# moja-row.net
KiCad netlist of a schematic drawn in EAGLE
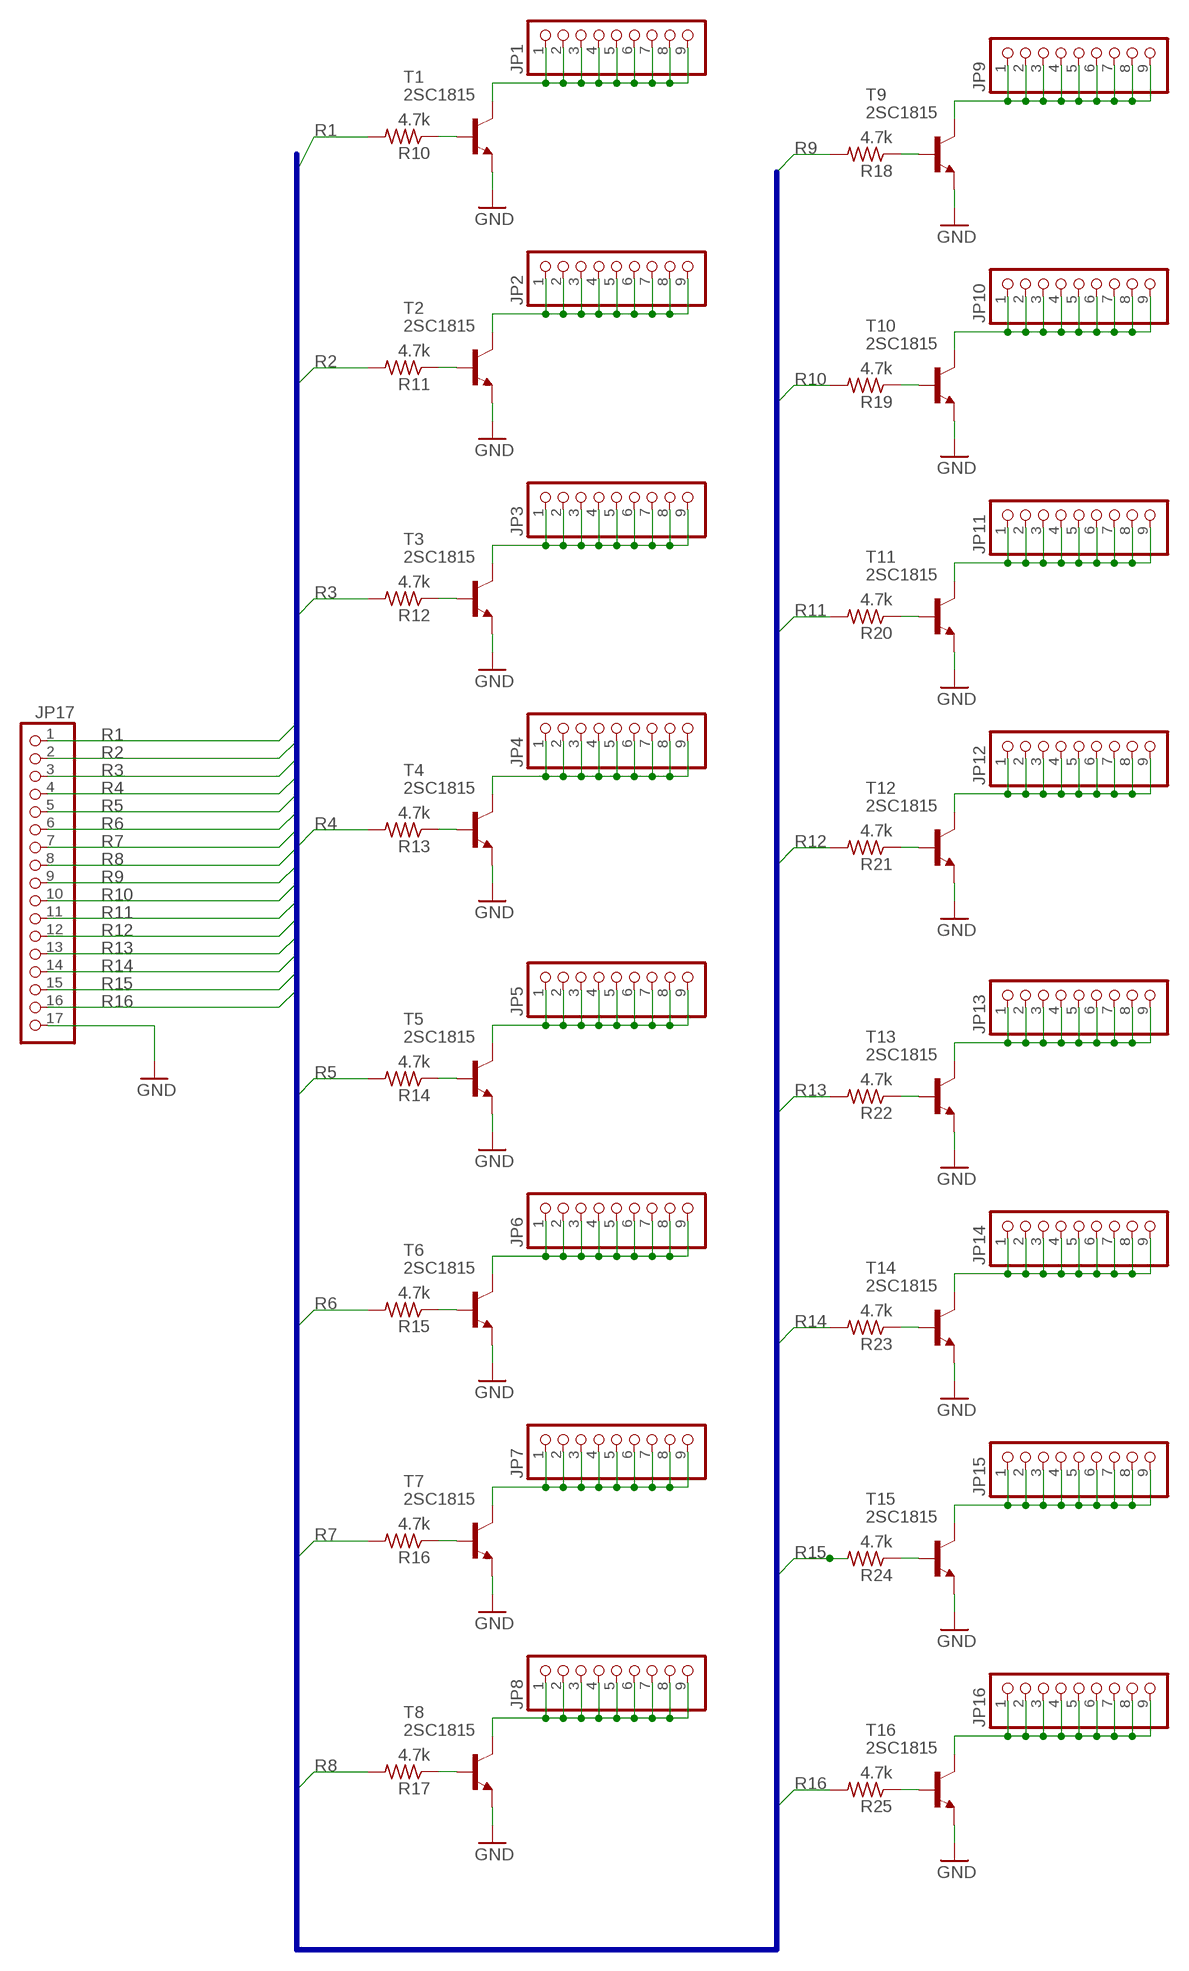
[diagram p0: schematic, sheet 1]

(export (version "E")
  (design (tool "Eeschema 10.0.6"))
  (components
    (comp (ref "JP1")
      (value "PINHD-1X9")
      (footprint "eagle-import:1X09")
      (libsource (lib "eagle-import") (part "PINHD-1X9"))
    )
    (comp (ref "JP2")
      (value "PINHD-1X9")
      (footprint "eagle-import:1X09")
      (libsource (lib "eagle-import") (part "PINHD-1X9"))
    )
    (comp (ref "JP3")
      (value "PINHD-1X9")
      (footprint "eagle-import:1X09")
      (libsource (lib "eagle-import") (part "PINHD-1X9"))
    )
    (comp (ref "JP4")
      (value "PINHD-1X9")
      (footprint "eagle-import:1X09")
      (libsource (lib "eagle-import") (part "PINHD-1X9"))
    )
    (comp (ref "JP5")
      (value "PINHD-1X9")
      (footprint "eagle-import:1X09")
      (libsource (lib "eagle-import") (part "PINHD-1X9"))
    )
    (comp (ref "JP6")
      (value "PINHD-1X9")
      (footprint "eagle-import:1X09")
      (libsource (lib "eagle-import") (part "PINHD-1X9"))
    )
    (comp (ref "JP7")
      (value "PINHD-1X9")
      (footprint "eagle-import:1X09")
      (libsource (lib "eagle-import") (part "PINHD-1X9"))
    )
    (comp (ref "JP8")
      (value "PINHD-1X9")
      (footprint "eagle-import:1X09")
      (libsource (lib "eagle-import") (part "PINHD-1X9"))
    )
    (comp (ref "JP9")
      (value "PINHD-1X9")
      (footprint "eagle-import:1X09")
      (libsource (lib "eagle-import") (part "PINHD-1X9"))
    )
    (comp (ref "JP10")
      (value "PINHD-1X9")
      (footprint "eagle-import:1X09")
      (libsource (lib "eagle-import") (part "PINHD-1X9"))
    )
    (comp (ref "JP11")
      (value "PINHD-1X9")
      (footprint "eagle-import:1X09")
      (libsource (lib "eagle-import") (part "PINHD-1X9"))
    )
    (comp (ref "JP12")
      (value "PINHD-1X9")
      (footprint "eagle-import:1X09")
      (libsource (lib "eagle-import") (part "PINHD-1X9"))
    )
    (comp (ref "JP13")
      (value "PINHD-1X9")
      (footprint "eagle-import:1X09")
      (libsource (lib "eagle-import") (part "PINHD-1X9"))
    )
    (comp (ref "JP14")
      (value "PINHD-1X9")
      (footprint "eagle-import:1X09")
      (libsource (lib "eagle-import") (part "PINHD-1X9"))
    )
    (comp (ref "JP15")
      (value "PINHD-1X9")
      (footprint "eagle-import:1X09")
      (libsource (lib "eagle-import") (part "PINHD-1X9"))
    )
    (comp (ref "JP16")
      (value "PINHD-1X9")
      (footprint "eagle-import:1X09")
      (libsource (lib "eagle-import") (part "PINHD-1X9"))
    )
    (comp (ref "JP17")
      (value "PINHD-1X17")
      (footprint "eagle-import:1X17")
      (libsource (lib "eagle-import") (part "PINHD-1X17"))
    )
    (comp (ref "R10")
      (value "4.7k")
      (footprint "eagle-import:0204V")
      (libsource (lib "eagle-import") (part "R-US_0204/2V"))
    )
    (comp (ref "R11")
      (value "4.7k")
      (footprint "eagle-import:0204V")
      (libsource (lib "eagle-import") (part "R-US_0204/2V"))
    )
    (comp (ref "R12")
      (value "4.7k")
      (footprint "eagle-import:0204V")
      (libsource (lib "eagle-import") (part "R-US_0204/2V"))
    )
    (comp (ref "R13")
      (value "4.7k")
      (footprint "eagle-import:0204V")
      (libsource (lib "eagle-import") (part "R-US_0204/2V"))
    )
    (comp (ref "R14")
      (value "4.7k")
      (footprint "eagle-import:0204V")
      (libsource (lib "eagle-import") (part "R-US_0204/2V"))
    )
    (comp (ref "R15")
      (value "4.7k")
      (footprint "eagle-import:0204V")
      (libsource (lib "eagle-import") (part "R-US_0204/2V"))
    )
    (comp (ref "R16")
      (value "4.7k")
      (footprint "eagle-import:0204V")
      (libsource (lib "eagle-import") (part "R-US_0204/2V"))
    )
    (comp (ref "R17")
      (value "4.7k")
      (footprint "eagle-import:0204V")
      (libsource (lib "eagle-import") (part "R-US_0204/2V"))
    )
    (comp (ref "R18")
      (value "4.7k")
      (footprint "eagle-import:0204V")
      (libsource (lib "eagle-import") (part "R-US_0204/2V"))
    )
    (comp (ref "R19")
      (value "4.7k")
      (footprint "eagle-import:0204V")
      (libsource (lib "eagle-import") (part "R-US_0204/2V"))
    )
    (comp (ref "R20")
      (value "4.7k")
      (footprint "eagle-import:0204V")
      (libsource (lib "eagle-import") (part "R-US_0204/2V"))
    )
    (comp (ref "R21")
      (value "4.7k")
      (footprint "eagle-import:0204V")
      (libsource (lib "eagle-import") (part "R-US_0204/2V"))
    )
    (comp (ref "R22")
      (value "4.7k")
      (footprint "eagle-import:0204V")
      (libsource (lib "eagle-import") (part "R-US_0204/2V"))
    )
    (comp (ref "R23")
      (value "4.7k")
      (footprint "eagle-import:0204V")
      (libsource (lib "eagle-import") (part "R-US_0204/2V"))
    )
    (comp (ref "R24")
      (value "4.7k")
      (footprint "eagle-import:0204V")
      (libsource (lib "eagle-import") (part "R-US_0204/2V"))
    )
    (comp (ref "R25")
      (value "4.7k")
      (footprint "eagle-import:0204V")
      (libsource (lib "eagle-import") (part "R-US_0204/2V"))
    )
    (comp (ref "T1")
      (value "2SC1815")
      (footprint "eagle-import:TO92-ECB")
      (libsource (lib "eagle-import") (part "2SC1815"))
    )
    (comp (ref "T2")
      (value "2SC1815")
      (footprint "eagle-import:TO92-ECB")
      (libsource (lib "eagle-import") (part "2SC1815"))
    )
    (comp (ref "T3")
      (value "2SC1815")
      (footprint "eagle-import:TO92-ECB")
      (libsource (lib "eagle-import") (part "2SC1815"))
    )
    (comp (ref "T4")
      (value "2SC1815")
      (footprint "eagle-import:TO92-ECB")
      (libsource (lib "eagle-import") (part "2SC1815"))
    )
    (comp (ref "T5")
      (value "2SC1815")
      (footprint "eagle-import:TO92-ECB")
      (libsource (lib "eagle-import") (part "2SC1815"))
    )
    (comp (ref "T6")
      (value "2SC1815")
      (footprint "eagle-import:TO92-ECB")
      (libsource (lib "eagle-import") (part "2SC1815"))
    )
    (comp (ref "T7")
      (value "2SC1815")
      (footprint "eagle-import:TO92-ECB")
      (libsource (lib "eagle-import") (part "2SC1815"))
    )
    (comp (ref "T8")
      (value "2SC1815")
      (footprint "eagle-import:TO92-ECB")
      (libsource (lib "eagle-import") (part "2SC1815"))
    )
    (comp (ref "T9")
      (value "2SC1815")
      (footprint "eagle-import:TO92-ECB")
      (libsource (lib "eagle-import") (part "2SC1815"))
    )
    (comp (ref "T10")
      (value "2SC1815")
      (footprint "eagle-import:TO92-ECB")
      (libsource (lib "eagle-import") (part "2SC1815"))
    )
    (comp (ref "T11")
      (value "2SC1815")
      (footprint "eagle-import:TO92-ECB")
      (libsource (lib "eagle-import") (part "2SC1815"))
    )
    (comp (ref "T12")
      (value "2SC1815")
      (footprint "eagle-import:TO92-ECB")
      (libsource (lib "eagle-import") (part "2SC1815"))
    )
    (comp (ref "T13")
      (value "2SC1815")
      (footprint "eagle-import:TO92-ECB")
      (libsource (lib "eagle-import") (part "2SC1815"))
    )
    (comp (ref "T14")
      (value "2SC1815")
      (footprint "eagle-import:TO92-ECB")
      (libsource (lib "eagle-import") (part "2SC1815"))
    )
    (comp (ref "T15")
      (value "2SC1815")
      (footprint "eagle-import:TO92-ECB")
      (libsource (lib "eagle-import") (part "2SC1815"))
    )
    (comp (ref "T16")
      (value "2SC1815")
      (footprint "eagle-import:TO92-ECB")
      (libsource (lib "eagle-import") (part "2SC1815"))
    )
  )
  (nets
    (net (code "1") (name "/R1") (class "Default")
      (node (ref "JP17") (pin "1") (pinfunction "1_1") (pintype "passive"))
      (node (ref "R10") (pin "2") (pinfunction "2_2") (pintype "passive"))
    )
    (net (code "2") (name "/R2") (class "Default")
      (node (ref "JP17") (pin "2") (pinfunction "2_2") (pintype "passive"))
      (node (ref "R11") (pin "2") (pinfunction "2_2") (pintype "passive"))
    )
    (net (code "3") (name "/R3") (class "Default")
      (node (ref "JP17") (pin "3") (pinfunction "3_3") (pintype "passive"))
      (node (ref "R12") (pin "2") (pinfunction "2_2") (pintype "passive"))
    )
    (net (code "4") (name "/R4") (class "Default")
      (node (ref "JP17") (pin "4") (pinfunction "4_4") (pintype "passive"))
      (node (ref "R13") (pin "2") (pinfunction "2_2") (pintype "passive"))
    )
    (net (code "5") (name "/R5") (class "Default")
      (node (ref "JP17") (pin "5") (pinfunction "5_5") (pintype "passive"))
      (node (ref "R14") (pin "2") (pinfunction "2_2") (pintype "passive"))
    )
    (net (code "6") (name "/R6") (class "Default")
      (node (ref "JP17") (pin "6") (pinfunction "6_6") (pintype "passive"))
      (node (ref "R15") (pin "2") (pinfunction "2_2") (pintype "passive"))
    )
    (net (code "7") (name "/R7") (class "Default")
      (node (ref "JP17") (pin "7") (pinfunction "7_7") (pintype "passive"))
      (node (ref "R16") (pin "2") (pinfunction "2_2") (pintype "passive"))
    )
    (net (code "8") (name "/R8") (class "Default")
      (node (ref "JP17") (pin "8") (pinfunction "8_8") (pintype "passive"))
      (node (ref "R17") (pin "2") (pinfunction "2_2") (pintype "passive"))
    )
    (net (code "9") (name "/R9") (class "Default")
      (node (ref "JP17") (pin "9") (pinfunction "9_9") (pintype "passive"))
      (node (ref "R18") (pin "2") (pinfunction "2_2") (pintype "passive"))
    )
    (net (code "10") (name "/R10") (class "Default")
      (node (ref "JP17") (pin "10") (pinfunction "10_10") (pintype "passive"))
      (node (ref "R19") (pin "2") (pinfunction "2_2") (pintype "passive"))
    )
    (net (code "11") (name "/R11") (class "Default")
      (node (ref "JP17") (pin "11") (pinfunction "11_11") (pintype "passive"))
      (node (ref "R20") (pin "2") (pinfunction "2_2") (pintype "passive"))
    )
    (net (code "12") (name "/R12") (class "Default")
      (node (ref "JP17") (pin "12") (pinfunction "12_12") (pintype "passive"))
      (node (ref "R21") (pin "2") (pinfunction "2_2") (pintype "passive"))
    )
    (net (code "13") (name "/R13") (class "Default")
      (node (ref "JP17") (pin "13") (pinfunction "13_13") (pintype "passive"))
      (node (ref "R22") (pin "2") (pinfunction "2_2") (pintype "passive"))
    )
    (net (code "14") (name "/R14") (class "Default")
      (node (ref "JP17") (pin "14") (pinfunction "14_14") (pintype "passive"))
      (node (ref "R23") (pin "2") (pinfunction "2_2") (pintype "passive"))
    )
    (net (code "15") (name "/R15") (class "Default")
      (node (ref "JP17") (pin "15") (pinfunction "15_15") (pintype "passive"))
      (node (ref "R24") (pin "2") (pinfunction "2_2") (pintype "passive"))
    )
    (net (code "16") (name "/R16") (class "Default")
      (node (ref "JP17") (pin "16") (pinfunction "16_16") (pintype "passive"))
      (node (ref "R25") (pin "2") (pinfunction "2_2") (pintype "passive"))
    )
    (net (code "17") (name "GND") (class "Default")
      (node (ref "JP17") (pin "17") (pinfunction "17_17") (pintype "passive"))
      (node (ref "T1") (pin "E") (pinfunction "E_E") (pintype "passive"))
      (node (ref "T10") (pin "E") (pinfunction "E_E") (pintype "passive"))
      (node (ref "T11") (pin "E") (pinfunction "E_E") (pintype "passive"))
      (node (ref "T12") (pin "E") (pinfunction "E_E") (pintype "passive"))
      (node (ref "T13") (pin "E") (pinfunction "E_E") (pintype "passive"))
      (node (ref "T14") (pin "E") (pinfunction "E_E") (pintype "passive"))
      (node (ref "T15") (pin "E") (pinfunction "E_E") (pintype "passive"))
      (node (ref "T16") (pin "E") (pinfunction "E_E") (pintype "passive"))
      (node (ref "T2") (pin "E") (pinfunction "E_E") (pintype "passive"))
      (node (ref "T3") (pin "E") (pinfunction "E_E") (pintype "passive"))
      (node (ref "T4") (pin "E") (pinfunction "E_E") (pintype "passive"))
      (node (ref "T5") (pin "E") (pinfunction "E_E") (pintype "passive"))
      (node (ref "T6") (pin "E") (pinfunction "E_E") (pintype "passive"))
      (node (ref "T7") (pin "E") (pinfunction "E_E") (pintype "passive"))
      (node (ref "T8") (pin "E") (pinfunction "E_E") (pintype "passive"))
      (node (ref "T9") (pin "E") (pinfunction "E_E") (pintype "passive"))
    )
    (net (code "18") (name "Net-(JP1-Pad1)") (class "Default")
      (node (ref "JP1") (pin "1") (pinfunction "1_1") (pintype "passive"))
      (node (ref "JP1") (pin "2") (pinfunction "2_2") (pintype "passive"))
      (node (ref "JP1") (pin "3") (pinfunction "3_3") (pintype "passive"))
      (node (ref "JP1") (pin "4") (pinfunction "4_4") (pintype "passive"))
      (node (ref "JP1") (pin "5") (pinfunction "5_5") (pintype "passive"))
      (node (ref "JP1") (pin "6") (pinfunction "6_6") (pintype "passive"))
      (node (ref "JP1") (pin "7") (pinfunction "7_7") (pintype "passive"))
      (node (ref "JP1") (pin "8") (pinfunction "8_8") (pintype "passive"))
      (node (ref "JP1") (pin "9") (pinfunction "9_9") (pintype "passive"))
      (node (ref "T1") (pin "C") (pinfunction "C_C") (pintype "passive"))
    )
    (net (code "19") (name "Net-(JP2-Pad1)") (class "Default")
      (node (ref "JP2") (pin "1") (pinfunction "1_1") (pintype "passive"))
      (node (ref "JP2") (pin "2") (pinfunction "2_2") (pintype "passive"))
      (node (ref "JP2") (pin "3") (pinfunction "3_3") (pintype "passive"))
      (node (ref "JP2") (pin "4") (pinfunction "4_4") (pintype "passive"))
      (node (ref "JP2") (pin "5") (pinfunction "5_5") (pintype "passive"))
      (node (ref "JP2") (pin "6") (pinfunction "6_6") (pintype "passive"))
      (node (ref "JP2") (pin "7") (pinfunction "7_7") (pintype "passive"))
      (node (ref "JP2") (pin "8") (pinfunction "8_8") (pintype "passive"))
      (node (ref "JP2") (pin "9") (pinfunction "9_9") (pintype "passive"))
      (node (ref "T2") (pin "C") (pinfunction "C_C") (pintype "passive"))
    )
    (net (code "20") (name "Net-(JP3-Pad1)") (class "Default")
      (node (ref "JP3") (pin "1") (pinfunction "1_1") (pintype "passive"))
      (node (ref "JP3") (pin "2") (pinfunction "2_2") (pintype "passive"))
      (node (ref "JP3") (pin "3") (pinfunction "3_3") (pintype "passive"))
      (node (ref "JP3") (pin "4") (pinfunction "4_4") (pintype "passive"))
      (node (ref "JP3") (pin "5") (pinfunction "5_5") (pintype "passive"))
      (node (ref "JP3") (pin "6") (pinfunction "6_6") (pintype "passive"))
      (node (ref "JP3") (pin "7") (pinfunction "7_7") (pintype "passive"))
      (node (ref "JP3") (pin "8") (pinfunction "8_8") (pintype "passive"))
      (node (ref "JP3") (pin "9") (pinfunction "9_9") (pintype "passive"))
      (node (ref "T3") (pin "C") (pinfunction "C_C") (pintype "passive"))
    )
    (net (code "21") (name "Net-(JP4-Pad1)") (class "Default")
      (node (ref "JP4") (pin "1") (pinfunction "1_1") (pintype "passive"))
      (node (ref "JP4") (pin "2") (pinfunction "2_2") (pintype "passive"))
      (node (ref "JP4") (pin "3") (pinfunction "3_3") (pintype "passive"))
      (node (ref "JP4") (pin "4") (pinfunction "4_4") (pintype "passive"))
      (node (ref "JP4") (pin "5") (pinfunction "5_5") (pintype "passive"))
      (node (ref "JP4") (pin "6") (pinfunction "6_6") (pintype "passive"))
      (node (ref "JP4") (pin "7") (pinfunction "7_7") (pintype "passive"))
      (node (ref "JP4") (pin "8") (pinfunction "8_8") (pintype "passive"))
      (node (ref "JP4") (pin "9") (pinfunction "9_9") (pintype "passive"))
      (node (ref "T4") (pin "C") (pinfunction "C_C") (pintype "passive"))
    )
    (net (code "22") (name "Net-(JP5-Pad1)") (class "Default")
      (node (ref "JP5") (pin "1") (pinfunction "1_1") (pintype "passive"))
      (node (ref "JP5") (pin "2") (pinfunction "2_2") (pintype "passive"))
      (node (ref "JP5") (pin "3") (pinfunction "3_3") (pintype "passive"))
      (node (ref "JP5") (pin "4") (pinfunction "4_4") (pintype "passive"))
      (node (ref "JP5") (pin "5") (pinfunction "5_5") (pintype "passive"))
      (node (ref "JP5") (pin "6") (pinfunction "6_6") (pintype "passive"))
      (node (ref "JP5") (pin "7") (pinfunction "7_7") (pintype "passive"))
      (node (ref "JP5") (pin "8") (pinfunction "8_8") (pintype "passive"))
      (node (ref "JP5") (pin "9") (pinfunction "9_9") (pintype "passive"))
      (node (ref "T5") (pin "C") (pinfunction "C_C") (pintype "passive"))
    )
    (net (code "23") (name "Net-(JP6-Pad1)") (class "Default")
      (node (ref "JP6") (pin "1") (pinfunction "1_1") (pintype "passive"))
      (node (ref "JP6") (pin "2") (pinfunction "2_2") (pintype "passive"))
      (node (ref "JP6") (pin "3") (pinfunction "3_3") (pintype "passive"))
      (node (ref "JP6") (pin "4") (pinfunction "4_4") (pintype "passive"))
      (node (ref "JP6") (pin "5") (pinfunction "5_5") (pintype "passive"))
      (node (ref "JP6") (pin "6") (pinfunction "6_6") (pintype "passive"))
      (node (ref "JP6") (pin "7") (pinfunction "7_7") (pintype "passive"))
      (node (ref "JP6") (pin "8") (pinfunction "8_8") (pintype "passive"))
      (node (ref "JP6") (pin "9") (pinfunction "9_9") (pintype "passive"))
      (node (ref "T6") (pin "C") (pinfunction "C_C") (pintype "passive"))
    )
    (net (code "24") (name "Net-(JP7-Pad1)") (class "Default")
      (node (ref "JP7") (pin "1") (pinfunction "1_1") (pintype "passive"))
      (node (ref "JP7") (pin "2") (pinfunction "2_2") (pintype "passive"))
      (node (ref "JP7") (pin "3") (pinfunction "3_3") (pintype "passive"))
      (node (ref "JP7") (pin "4") (pinfunction "4_4") (pintype "passive"))
      (node (ref "JP7") (pin "5") (pinfunction "5_5") (pintype "passive"))
      (node (ref "JP7") (pin "6") (pinfunction "6_6") (pintype "passive"))
      (node (ref "JP7") (pin "7") (pinfunction "7_7") (pintype "passive"))
      (node (ref "JP7") (pin "8") (pinfunction "8_8") (pintype "passive"))
      (node (ref "JP7") (pin "9") (pinfunction "9_9") (pintype "passive"))
      (node (ref "T7") (pin "C") (pinfunction "C_C") (pintype "passive"))
    )
    (net (code "25") (name "Net-(JP8-Pad1)") (class "Default")
      (node (ref "JP8") (pin "1") (pinfunction "1_1") (pintype "passive"))
      (node (ref "JP8") (pin "2") (pinfunction "2_2") (pintype "passive"))
      (node (ref "JP8") (pin "3") (pinfunction "3_3") (pintype "passive"))
      (node (ref "JP8") (pin "4") (pinfunction "4_4") (pintype "passive"))
      (node (ref "JP8") (pin "5") (pinfunction "5_5") (pintype "passive"))
      (node (ref "JP8") (pin "6") (pinfunction "6_6") (pintype "passive"))
      (node (ref "JP8") (pin "7") (pinfunction "7_7") (pintype "passive"))
      (node (ref "JP8") (pin "8") (pinfunction "8_8") (pintype "passive"))
      (node (ref "JP8") (pin "9") (pinfunction "9_9") (pintype "passive"))
      (node (ref "T8") (pin "C") (pinfunction "C_C") (pintype "passive"))
    )
    (net (code "26") (name "Net-(JP9-Pad1)") (class "Default")
      (node (ref "JP9") (pin "1") (pinfunction "1_1") (pintype "passive"))
      (node (ref "JP9") (pin "2") (pinfunction "2_2") (pintype "passive"))
      (node (ref "JP9") (pin "3") (pinfunction "3_3") (pintype "passive"))
      (node (ref "JP9") (pin "4") (pinfunction "4_4") (pintype "passive"))
      (node (ref "JP9") (pin "5") (pinfunction "5_5") (pintype "passive"))
      (node (ref "JP9") (pin "6") (pinfunction "6_6") (pintype "passive"))
      (node (ref "JP9") (pin "7") (pinfunction "7_7") (pintype "passive"))
      (node (ref "JP9") (pin "8") (pinfunction "8_8") (pintype "passive"))
      (node (ref "JP9") (pin "9") (pinfunction "9_9") (pintype "passive"))
      (node (ref "T9") (pin "C") (pinfunction "C_C") (pintype "passive"))
    )
    (net (code "27") (name "Net-(JP10-Pad1)") (class "Default")
      (node (ref "JP10") (pin "1") (pinfunction "1_1") (pintype "passive"))
      (node (ref "JP10") (pin "2") (pinfunction "2_2") (pintype "passive"))
      (node (ref "JP10") (pin "3") (pinfunction "3_3") (pintype "passive"))
      (node (ref "JP10") (pin "4") (pinfunction "4_4") (pintype "passive"))
      (node (ref "JP10") (pin "5") (pinfunction "5_5") (pintype "passive"))
      (node (ref "JP10") (pin "6") (pinfunction "6_6") (pintype "passive"))
      (node (ref "JP10") (pin "7") (pinfunction "7_7") (pintype "passive"))
      (node (ref "JP10") (pin "8") (pinfunction "8_8") (pintype "passive"))
      (node (ref "JP10") (pin "9") (pinfunction "9_9") (pintype "passive"))
      (node (ref "T10") (pin "C") (pinfunction "C_C") (pintype "passive"))
    )
    (net (code "28") (name "Net-(JP11-Pad1)") (class "Default")
      (node (ref "JP11") (pin "1") (pinfunction "1_1") (pintype "passive"))
      (node (ref "JP11") (pin "2") (pinfunction "2_2") (pintype "passive"))
      (node (ref "JP11") (pin "3") (pinfunction "3_3") (pintype "passive"))
      (node (ref "JP11") (pin "4") (pinfunction "4_4") (pintype "passive"))
      (node (ref "JP11") (pin "5") (pinfunction "5_5") (pintype "passive"))
      (node (ref "JP11") (pin "6") (pinfunction "6_6") (pintype "passive"))
      (node (ref "JP11") (pin "7") (pinfunction "7_7") (pintype "passive"))
      (node (ref "JP11") (pin "8") (pinfunction "8_8") (pintype "passive"))
      (node (ref "JP11") (pin "9") (pinfunction "9_9") (pintype "passive"))
      (node (ref "T11") (pin "C") (pinfunction "C_C") (pintype "passive"))
    )
    (net (code "29") (name "Net-(JP12-Pad1)") (class "Default")
      (node (ref "JP12") (pin "1") (pinfunction "1_1") (pintype "passive"))
      (node (ref "JP12") (pin "2") (pinfunction "2_2") (pintype "passive"))
      (node (ref "JP12") (pin "3") (pinfunction "3_3") (pintype "passive"))
      (node (ref "JP12") (pin "4") (pinfunction "4_4") (pintype "passive"))
      (node (ref "JP12") (pin "5") (pinfunction "5_5") (pintype "passive"))
      (node (ref "JP12") (pin "6") (pinfunction "6_6") (pintype "passive"))
      (node (ref "JP12") (pin "7") (pinfunction "7_7") (pintype "passive"))
      (node (ref "JP12") (pin "8") (pinfunction "8_8") (pintype "passive"))
      (node (ref "JP12") (pin "9") (pinfunction "9_9") (pintype "passive"))
      (node (ref "T12") (pin "C") (pinfunction "C_C") (pintype "passive"))
    )
    (net (code "30") (name "Net-(JP13-Pad1)") (class "Default")
      (node (ref "JP13") (pin "1") (pinfunction "1_1") (pintype "passive"))
      (node (ref "JP13") (pin "2") (pinfunction "2_2") (pintype "passive"))
      (node (ref "JP13") (pin "3") (pinfunction "3_3") (pintype "passive"))
      (node (ref "JP13") (pin "4") (pinfunction "4_4") (pintype "passive"))
      (node (ref "JP13") (pin "5") (pinfunction "5_5") (pintype "passive"))
      (node (ref "JP13") (pin "6") (pinfunction "6_6") (pintype "passive"))
      (node (ref "JP13") (pin "7") (pinfunction "7_7") (pintype "passive"))
      (node (ref "JP13") (pin "8") (pinfunction "8_8") (pintype "passive"))
      (node (ref "JP13") (pin "9") (pinfunction "9_9") (pintype "passive"))
      (node (ref "T13") (pin "C") (pinfunction "C_C") (pintype "passive"))
    )
    (net (code "31") (name "Net-(JP14-Pad1)") (class "Default")
      (node (ref "JP14") (pin "1") (pinfunction "1_1") (pintype "passive"))
      (node (ref "JP14") (pin "2") (pinfunction "2_2") (pintype "passive"))
      (node (ref "JP14") (pin "3") (pinfunction "3_3") (pintype "passive"))
      (node (ref "JP14") (pin "4") (pinfunction "4_4") (pintype "passive"))
      (node (ref "JP14") (pin "5") (pinfunction "5_5") (pintype "passive"))
      (node (ref "JP14") (pin "6") (pinfunction "6_6") (pintype "passive"))
      (node (ref "JP14") (pin "7") (pinfunction "7_7") (pintype "passive"))
      (node (ref "JP14") (pin "8") (pinfunction "8_8") (pintype "passive"))
      (node (ref "JP14") (pin "9") (pinfunction "9_9") (pintype "passive"))
      (node (ref "T14") (pin "C") (pinfunction "C_C") (pintype "passive"))
    )
    (net (code "32") (name "Net-(JP15-Pad1)") (class "Default")
      (node (ref "JP15") (pin "1") (pinfunction "1_1") (pintype "passive"))
      (node (ref "JP15") (pin "2") (pinfunction "2_2") (pintype "passive"))
      (node (ref "JP15") (pin "3") (pinfunction "3_3") (pintype "passive"))
      (node (ref "JP15") (pin "4") (pinfunction "4_4") (pintype "passive"))
      (node (ref "JP15") (pin "5") (pinfunction "5_5") (pintype "passive"))
      (node (ref "JP15") (pin "6") (pinfunction "6_6") (pintype "passive"))
      (node (ref "JP15") (pin "7") (pinfunction "7_7") (pintype "passive"))
      (node (ref "JP15") (pin "8") (pinfunction "8_8") (pintype "passive"))
      (node (ref "JP15") (pin "9") (pinfunction "9_9") (pintype "passive"))
      (node (ref "T15") (pin "C") (pinfunction "C_C") (pintype "passive"))
    )
    (net (code "33") (name "Net-(JP16-Pad1)") (class "Default")
      (node (ref "JP16") (pin "1") (pinfunction "1_1") (pintype "passive"))
      (node (ref "JP16") (pin "2") (pinfunction "2_2") (pintype "passive"))
      (node (ref "JP16") (pin "3") (pinfunction "3_3") (pintype "passive"))
      (node (ref "JP16") (pin "4") (pinfunction "4_4") (pintype "passive"))
      (node (ref "JP16") (pin "5") (pinfunction "5_5") (pintype "passive"))
      (node (ref "JP16") (pin "6") (pinfunction "6_6") (pintype "passive"))
      (node (ref "JP16") (pin "7") (pinfunction "7_7") (pintype "passive"))
      (node (ref "JP16") (pin "8") (pinfunction "8_8") (pintype "passive"))
      (node (ref "JP16") (pin "9") (pinfunction "9_9") (pintype "passive"))
      (node (ref "T16") (pin "C") (pinfunction "C_C") (pintype "passive"))
    )
    (net (code "34") (name "Net-(R10-Pad1)") (class "Default")
      (node (ref "R10") (pin "1") (pinfunction "1_1") (pintype "passive"))
      (node (ref "T1") (pin "B") (pinfunction "B_B") (pintype "passive"))
    )
    (net (code "35") (name "Net-(R11-Pad1)") (class "Default")
      (node (ref "R11") (pin "1") (pinfunction "1_1") (pintype "passive"))
      (node (ref "T2") (pin "B") (pinfunction "B_B") (pintype "passive"))
    )
    (net (code "36") (name "Net-(R12-Pad1)") (class "Default")
      (node (ref "R12") (pin "1") (pinfunction "1_1") (pintype "passive"))
      (node (ref "T3") (pin "B") (pinfunction "B_B") (pintype "passive"))
    )
    (net (code "37") (name "Net-(R13-Pad1)") (class "Default")
      (node (ref "R13") (pin "1") (pinfunction "1_1") (pintype "passive"))
      (node (ref "T4") (pin "B") (pinfunction "B_B") (pintype "passive"))
    )
    (net (code "38") (name "Net-(R14-Pad1)") (class "Default")
      (node (ref "R14") (pin "1") (pinfunction "1_1") (pintype "passive"))
      (node (ref "T5") (pin "B") (pinfunction "B_B") (pintype "passive"))
    )
    (net (code "39") (name "Net-(R15-Pad1)") (class "Default")
      (node (ref "R15") (pin "1") (pinfunction "1_1") (pintype "passive"))
      (node (ref "T6") (pin "B") (pinfunction "B_B") (pintype "passive"))
    )
    (net (code "40") (name "Net-(R16-Pad1)") (class "Default")
      (node (ref "R16") (pin "1") (pinfunction "1_1") (pintype "passive"))
      (node (ref "T7") (pin "B") (pinfunction "B_B") (pintype "passive"))
    )
    (net (code "41") (name "Net-(R17-Pad1)") (class "Default")
      (node (ref "R17") (pin "1") (pinfunction "1_1") (pintype "passive"))
      (node (ref "T8") (pin "B") (pinfunction "B_B") (pintype "passive"))
    )
    (net (code "42") (name "Net-(R18-Pad1)") (class "Default")
      (node (ref "R18") (pin "1") (pinfunction "1_1") (pintype "passive"))
      (node (ref "T9") (pin "B") (pinfunction "B_B") (pintype "passive"))
    )
    (net (code "43") (name "Net-(R19-Pad1)") (class "Default")
      (node (ref "R19") (pin "1") (pinfunction "1_1") (pintype "passive"))
      (node (ref "T10") (pin "B") (pinfunction "B_B") (pintype "passive"))
    )
    (net (code "44") (name "Net-(R20-Pad1)") (class "Default")
      (node (ref "R20") (pin "1") (pinfunction "1_1") (pintype "passive"))
      (node (ref "T11") (pin "B") (pinfunction "B_B") (pintype "passive"))
    )
    (net (code "45") (name "Net-(R21-Pad1)") (class "Default")
      (node (ref "R21") (pin "1") (pinfunction "1_1") (pintype "passive"))
      (node (ref "T12") (pin "B") (pinfunction "B_B") (pintype "passive"))
    )
    (net (code "46") (name "Net-(R22-Pad1)") (class "Default")
      (node (ref "R22") (pin "1") (pinfunction "1_1") (pintype "passive"))
      (node (ref "T13") (pin "B") (pinfunction "B_B") (pintype "passive"))
    )
    (net (code "47") (name "Net-(R23-Pad1)") (class "Default")
      (node (ref "R23") (pin "1") (pinfunction "1_1") (pintype "passive"))
      (node (ref "T14") (pin "B") (pinfunction "B_B") (pintype "passive"))
    )
    (net (code "48") (name "Net-(R24-Pad1)") (class "Default")
      (node (ref "R24") (pin "1") (pinfunction "1_1") (pintype "passive"))
      (node (ref "T15") (pin "B") (pinfunction "B_B") (pintype "passive"))
    )
    (net (code "49") (name "Net-(R25-Pad1)") (class "Default")
      (node (ref "R25") (pin "1") (pinfunction "1_1") (pintype "passive"))
      (node (ref "T16") (pin "B") (pinfunction "B_B") (pintype "passive"))
    )
  )
)
